# Sheet1.net
KiCad netlist of a schematic drawn in Altium Designer
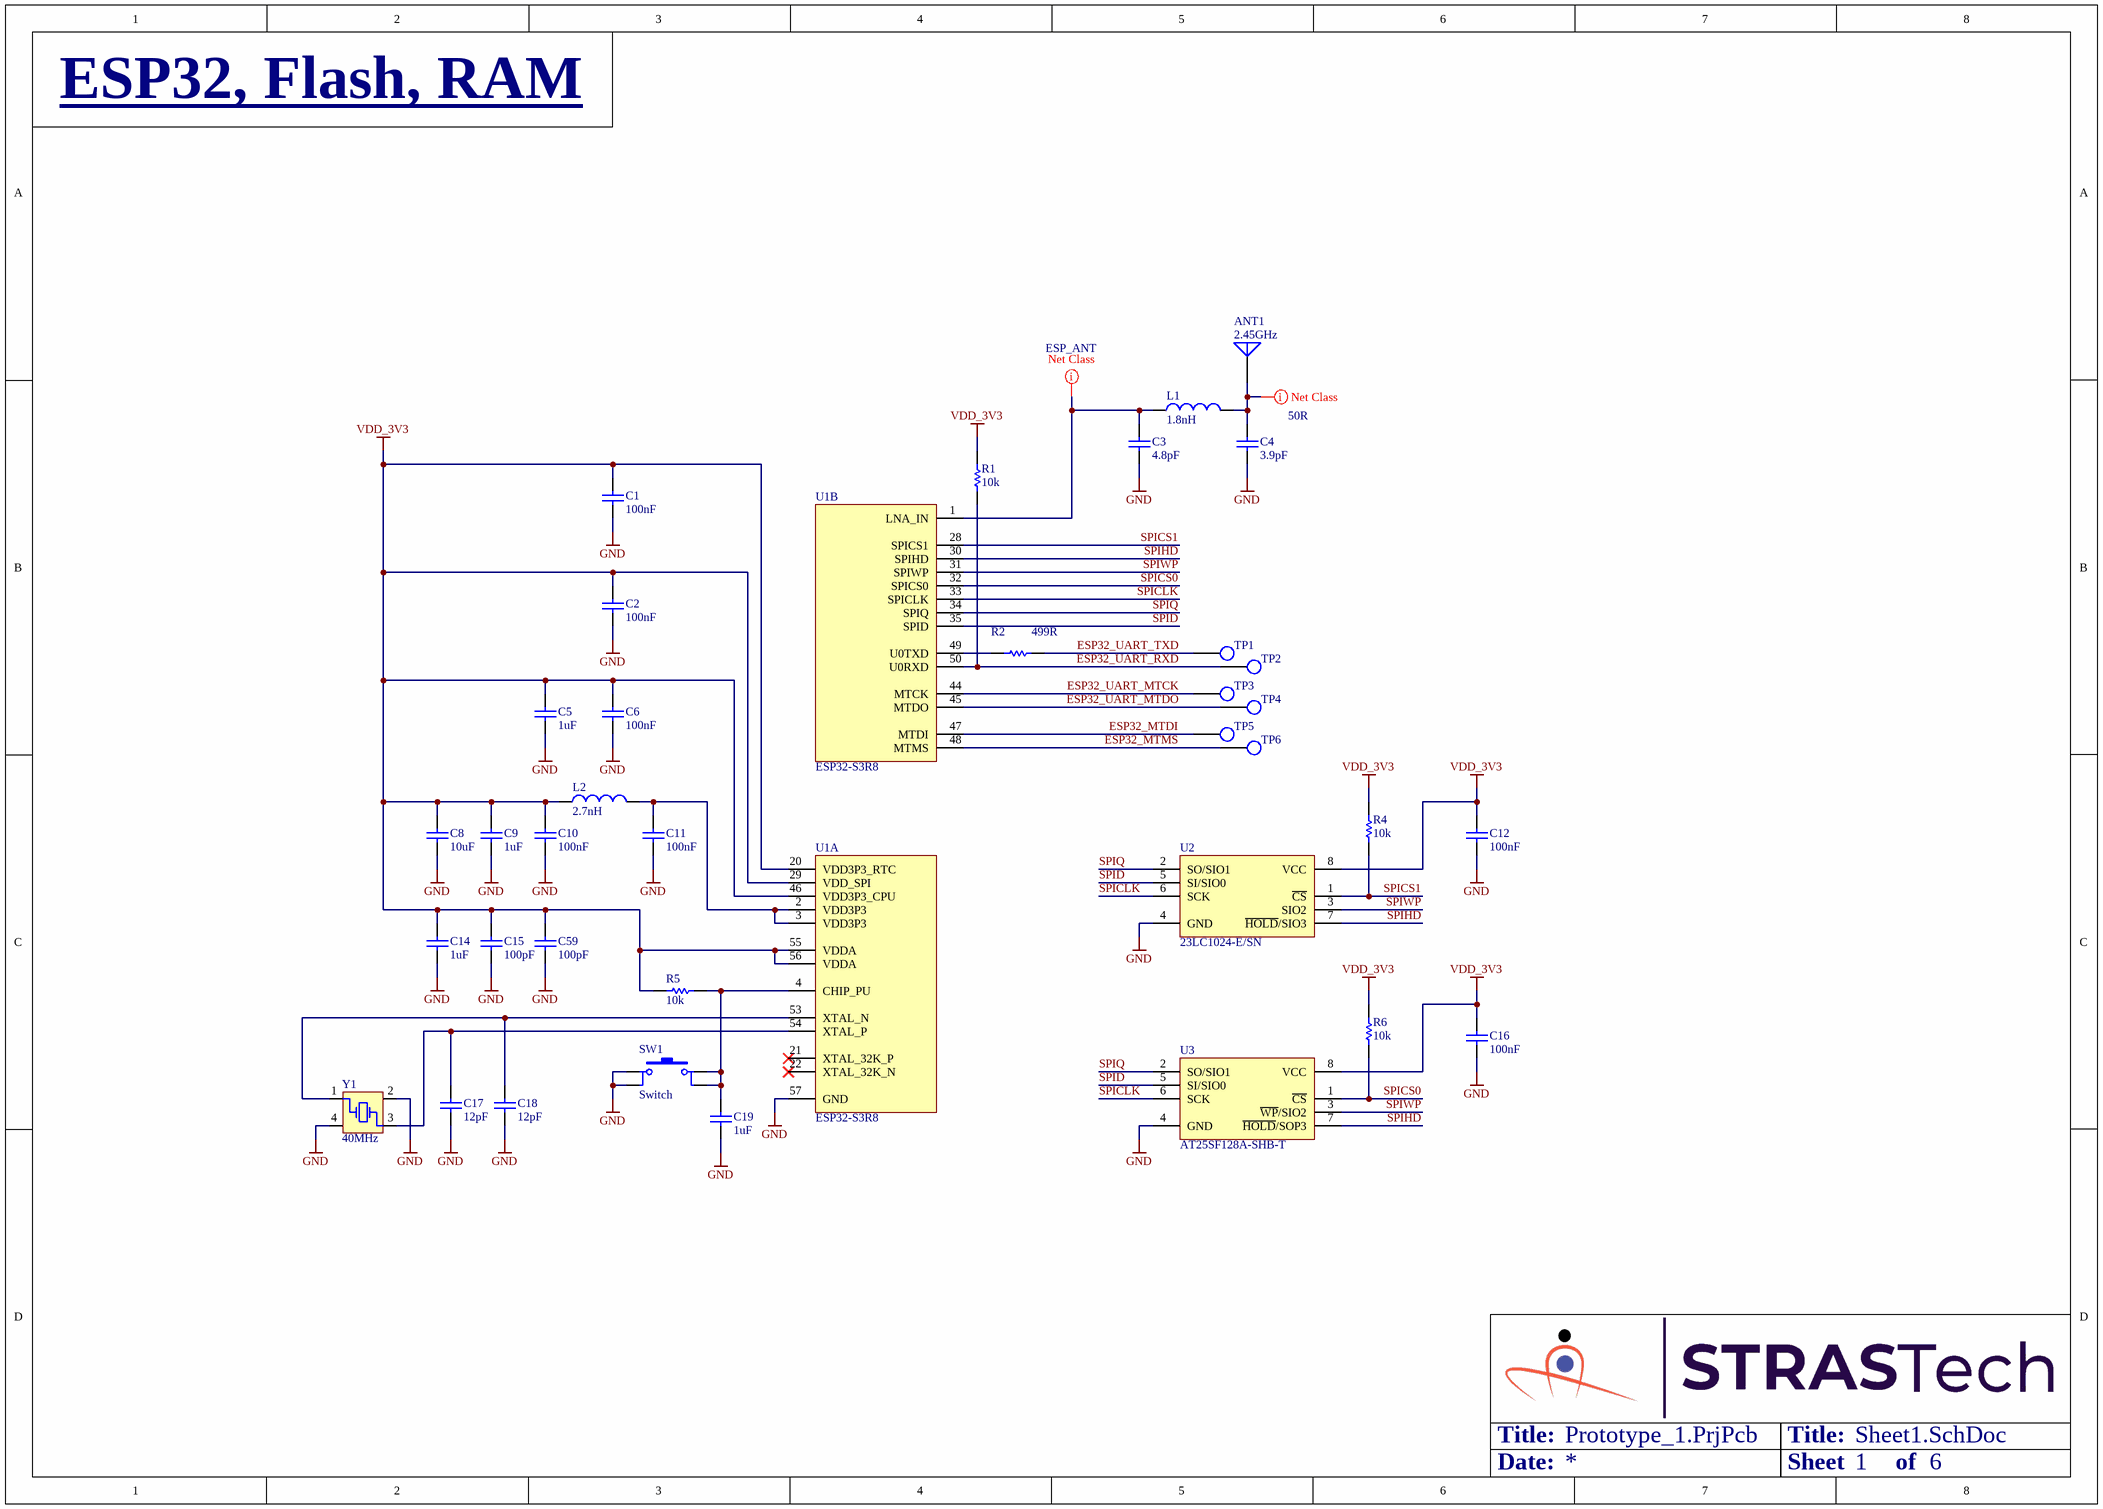
[diagram p0: Sheet1.SchDoc]

(export (version "E")
  (design (tool "Eeschema 10.0.6"))
  (components
    (comp (ref "ANT1")
      (value "2.45GHz")
      (footprint "ANT,PCB,IFA,2.45GHZ")
      (description "2.4-GHz Inverted F Antenna")
      (fields (field (name "CREATEDBY") "Judd Foster"))
      (libsource (lib "symbols") (part "ANT,2.45GHz,IFA,PCB"))
    )
    (comp (ref "C1")
      (value "100nF")
      (footprint "Cap,SMD,0402")
      (description "0.1µF ±10% 25V Ceramic Capacitor X7R 0402 (1005 Metric)")
      (fields
        (field (name "VENDOR PART NUMBER") "490-14603-1-ND")
        (field (name "MANUFACTURER") "Murata Electronics")
        (field (name "CREATEDBY") "Judd Foster")
      )
      (libsource (lib "symbols") (part "CAP,Cer,100nF,25VDC,X7R,0402"))
    )
    (comp (ref "C2")
      (value "100nF")
      (footprint "Cap,SMD,0402")
      (description "0.1µF ±10% 25V Ceramic Capacitor X7R 0402 (1005 Metric)")
      (fields
        (field (name "VENDOR PART NUMBER") "490-14603-1-ND")
        (field (name "MANUFACTURER") "Murata Electronics")
        (field (name "CREATEDBY") "Judd Foster")
      )
      (libsource (lib "symbols") (part "CAP,Cer,100nF,25VDC,X7R,0402"))
    )
    (comp (ref "C3")
      (value "4.8pF")
      (footprint "Cap,SMD,0402")
      (description "4.8 pF ±0.25pF 50V Ceramic Capacitor C0G, NP0 0402 (1005 Metric)")
      (fields
        (field (name "VENDOR PART NUMBER") "490-17481-1-ND")
        (field (name "MANUFACTURER") "Murata Electronics")
        (field (name "CREATEDBY") "Judd Foster")
      )
      (libsource (lib "symbols") (part "CAP,Cer,4.8pF,50VDC,C0G/NP0,0402"))
    )
    (comp (ref "C4")
      (value "3.9pF")
      (footprint "Cap,SMD,0402")
      (description "3.9 pF ±0.1pF 50V Ceramic Capacitor C0G, NP0 0402 (1005 Metric)")
      (fields
        (field (name "VENDOR PART NUMBER") "399-CBR04C399B5GACCT-ND")
        (field (name "MANUFACTURER") "KEMET")
        (field (name "CREATEDBY") "Judd Foster")
      )
      (libsource (lib "symbols") (part "CAP,Cer,3.9pF,50VDC,C0G/NP0,0402"))
    )
    (comp (ref "C5")
      (value "1uF")
      (footprint "Cap,SMD,0402")
      (description "1 µF ±10% 35V Ceramic Capacitor X5R 0402 (1005 Metric)")
      (fields
        (field (name "VENDOR PART NUMBER") "445-9073-1-ND")
        (field (name "MANUFACTURER") "TDK Corporation")
        (field (name "CREATEDBY") "Judd Foster")
      )
      (libsource (lib "symbols") (part "CAP,Cer,1uF,35VDC,X5R,0402"))
    )
    (comp (ref "C6")
      (value "100nF")
      (footprint "Cap,SMD,0402")
      (description "0.1µF ±10% 25V Ceramic Capacitor X7R 0402 (1005 Metric)")
      (fields
        (field (name "VENDOR PART NUMBER") "490-14603-1-ND")
        (field (name "MANUFACTURER") "Murata Electronics")
        (field (name "CREATEDBY") "Judd Foster")
      )
      (libsource (lib "symbols") (part "CAP,Cer,100nF,25VDC,X7R,0402"))
    )
    (comp (ref "C8")
      (value "10uF")
      (footprint "Cap,SMD,0402")
      (description "10 µF ±20% 10V Ceramic Capacitor X5R 0402 (1005 Metric)")
      (fields
        (field (name "VENDOR PART NUMBER") "1276-1450-1-ND")
        (field (name "MANUFACTURER") "Samsung Electro-Mechanics")
        (field (name "CREATEDBY") "Judd Foster")
      )
      (libsource (lib "symbols") (part "CAP,Cer,10uF,10VDC,X5R,0402"))
    )
    (comp (ref "C9")
      (value "1uF")
      (footprint "Cap,SMD,0402")
      (description "1 µF ±10% 35V Ceramic Capacitor X5R 0402 (1005 Metric)")
      (fields
        (field (name "VENDOR PART NUMBER") "445-9073-1-ND")
        (field (name "MANUFACTURER") "TDK Corporation")
        (field (name "CREATEDBY") "Judd Foster")
      )
      (libsource (lib "symbols") (part "CAP,Cer,1uF,35VDC,X5R,0402"))
    )
    (comp (ref "C10")
      (value "100nF")
      (footprint "Cap,SMD,0402")
      (description "0.1µF ±10% 25V Ceramic Capacitor X7R 0402 (1005 Metric)")
      (fields
        (field (name "VENDOR PART NUMBER") "490-14603-1-ND")
        (field (name "MANUFACTURER") "Murata Electronics")
        (field (name "CREATEDBY") "Judd Foster")
      )
      (libsource (lib "symbols") (part "CAP,Cer,100nF,25VDC,X7R,0402"))
    )
    (comp (ref "C11")
      (value "100nF")
      (footprint "Cap,SMD,0402")
      (description "0.1µF ±10% 25V Ceramic Capacitor X7R 0402 (1005 Metric)")
      (fields
        (field (name "VENDOR PART NUMBER") "490-14603-1-ND")
        (field (name "MANUFACTURER") "Murata Electronics")
        (field (name "CREATEDBY") "Judd Foster")
      )
      (libsource (lib "symbols") (part "CAP,Cer,100nF,25VDC,X7R,0402"))
    )
    (comp (ref "C12")
      (value "100nF")
      (footprint "Cap,SMD,0402")
      (description "0.1µF ±10% 25V Ceramic Capacitor X7R 0402 (1005 Metric)")
      (fields
        (field (name "VENDOR PART NUMBER") "490-14603-1-ND")
        (field (name "MANUFACTURER") "Murata Electronics")
        (field (name "CREATEDBY") "Judd Foster")
      )
      (libsource (lib "symbols") (part "CAP,Cer,100nF,25VDC,X7R,0402"))
    )
    (comp (ref "C14")
      (value "1uF")
      (footprint "Cap,SMD,0402")
      (description "1 µF ±10% 35V Ceramic Capacitor X5R 0402 (1005 Metric)")
      (fields
        (field (name "VENDOR PART NUMBER") "445-9073-1-ND")
        (field (name "MANUFACTURER") "TDK Corporation")
        (field (name "CREATEDBY") "Judd Foster")
      )
      (libsource (lib "symbols") (part "CAP,Cer,1uF,35VDC,X5R,0402"))
    )
    (comp (ref "C15")
      (value "100pF")
      (footprint "Cap,SMD,0402")
      (description "100pF ±5% 50V Ceramic Capacitor C0G, NP0 0402 (1005 Metric)")
      (fields
        (field (name "VENDOR PART NUMBER") "490-10669-1-ND")
        (field (name "MANUFACTURER") "Murata Electronics")
        (field (name "CREATEDBY") "Judd Foster")
      )
      (libsource (lib "symbols") (part "CAP,Cer,100pF,50VDC,C0G/NP0,0402"))
    )
    (comp (ref "C16")
      (value "100nF")
      (footprint "Cap,SMD,0402")
      (description "0.1µF ±10% 25V Ceramic Capacitor X7R 0402 (1005 Metric)")
      (fields
        (field (name "VENDOR PART NUMBER") "490-14603-1-ND")
        (field (name "MANUFACTURER") "Murata Electronics")
        (field (name "CREATEDBY") "Judd Foster")
      )
      (libsource (lib "symbols") (part "CAP,Cer,100nF,25VDC,X7R,0402"))
    )
    (comp (ref "C17")
      (value "12pF")
      (footprint "Cap,SMD,0402")
      (description "12pF ±5% 50V Ceramic Capacitor C0G, NP0 0402 (1005 Metric)")
      (fields
        (field (name "VENDOR PART NUMBER") "311-1016-1-ND")
        (field (name "MANUFACTURER") "Yageo")
        (field (name "CREATEDBY") "Judd Foster")
      )
      (libsource (lib "symbols") (part "CAP,Cer,12pF,50VDC,C0G/NP0,0402"))
    )
    (comp (ref "C18")
      (value "12pF")
      (footprint "Cap,SMD,0402")
      (description "12pF ±5% 50V Ceramic Capacitor C0G, NP0 0402 (1005 Metric)")
      (fields
        (field (name "VENDOR PART NUMBER") "311-1016-1-ND")
        (field (name "MANUFACTURER") "Yageo")
        (field (name "CREATEDBY") "Judd Foster")
      )
      (libsource (lib "symbols") (part "CAP,Cer,12pF,50VDC,C0G/NP0,0402"))
    )
    (comp (ref "C19")
      (value "1uF")
      (footprint "Cap,SMD,0402")
      (description "1µF ±20% 6.3V Ceramic Capacitor X5R 0402 (1005 Metric)")
      (fields
        (field (name "VENDOR PART NUMBER") "1276-1235-1-ND")
        (field (name "MANUFACTURER") "Samsung Electro-Mechanics")
        (field (name "CREATEDBY") "Judd Foster")
      )
      (libsource (lib "symbols") (part "CAP,Cer,1uF,6.3VDC,X5R,0402"))
    )
    (comp (ref "C59")
      (value "100pF")
      (footprint "Cap,SMD,0402")
      (description "100pF ±5% 50V Ceramic Capacitor C0G, NP0 0402 (1005 Metric)")
      (fields
        (field (name "VENDOR PART NUMBER") "490-10669-1-ND")
        (field (name "MANUFACTURER") "Murata Electronics")
        (field (name "CREATEDBY") "Judd Foster")
      )
      (libsource (lib "symbols") (part "CAP,Cer,100pF,50VDC,C0G/NP0,0402"))
    )
    (comp (ref "L1")
      (value "1.8nH")
      (footprint "ind,0402")
      (description "1.8 nH Unshielded Multilayer Inductor 900 mA 100mOhm Max 0402 (1005 Metric)")
      (fields
        (field (name "VENDOR PART NUMBER") "490-1076-1-ND")
        (field (name "MANUFACTURER") "Murata Electronics")
        (field (name "CREATEDBY") "Judd Foster")
      )
      (libsource (lib "symbols") (part "IND,1.8nH,900mA,Multilayer,0402"))
    )
    (comp (ref "L2")
      (value "2.7nH")
      (footprint "ind,0402")
      (description "2.7nH Unshielded Multilayer Inductor 800mA 150mOhm Max 0402 (1005 Metric)")
      (fields
        (field (name "VENDOR PART NUMBER") "490-2615-1-ND")
        (field (name "MANUFACTURER") "Murata Electronics")
        (field (name "CREATEDBY") "Judd Foster")
      )
      (libsource (lib "symbols") (part "IND,2.7nH,800mA,Multilayer,0402"))
    )
    (comp (ref "R1")
      (value "10k")
      (footprint "RES,0402")
      (description "10 kOhms ±5% 0.063W, 1/16W Chip Resistor 0402 (1005 Metric) Automotive AEC-Q200 Thick Film")
      (fields
        (field (name "VENDOR PART NUMBER") "RMCF0402JT10K0CT-ND")
        (field (name "MANUFACTURER") "Stackpole Electronics Inc")
        (field (name "CREATEDBY") "Judd Foster")
      )
      (libsource (lib "symbols") (part "RES,10k,5%,0.063W,0402"))
    )
    (comp (ref "R2")
      (value "499R")
      (footprint "RES,0402")
      (description "499 Ohms ±1% 0.063W, 1/16W Chip Resistor 0402 (1005 Metric) Automotive AEC-Q200 Thick Film")
      (fields
        (field (name "MANUFACTURER") "Stackpole Electronics Inc")
        (field (name "MANUFACTURER PART NUMBER") "RMCF0402FT499R")
        (field (name "CREATEDBY") "Judd Foster")
      )
      (libsource (lib "symbols") (part "RES,499R,1%,0.063W,0402"))
    )
    (comp (ref "R4")
      (value "10k")
      (footprint "RES,0402")
      (description "10 kOhms ±5% 0.063W, 1/16W Chip Resistor 0402 (1005 Metric) Automotive AEC-Q200 Thick Film")
      (fields
        (field (name "VENDOR PART NUMBER") "RMCF0402JT10K0CT-ND")
        (field (name "MANUFACTURER") "Stackpole Electronics Inc")
        (field (name "CREATEDBY") "Judd Foster")
      )
      (libsource (lib "symbols") (part "RES,10k,5%,0.063W,0402"))
    )
    (comp (ref "R5")
      (value "10k")
      (footprint "RES,0402")
      (description "10 kOhms ±5% 0.063W, 1/16W Chip Resistor 0402 (1005 Metric) Automotive AEC-Q200 Thick Film")
      (fields
        (field (name "VENDOR PART NUMBER") "RMCF0402JT10K0CT-ND")
        (field (name "MANUFACTURER") "Stackpole Electronics Inc")
        (field (name "CREATEDBY") "Judd Foster")
      )
      (libsource (lib "symbols") (part "RES,10k,5%,0.063W,0402"))
    )
    (comp (ref "R6")
      (value "10k")
      (footprint "RES,0402")
      (description "10 kOhms ±5% 0.063W, 1/16W Chip Resistor 0402 (1005 Metric) Automotive AEC-Q200 Thick Film")
      (fields
        (field (name "VENDOR PART NUMBER") "RMCF0402JT10K0CT-ND")
        (field (name "MANUFACTURER") "Stackpole Electronics Inc")
        (field (name "CREATEDBY") "Judd Foster")
      )
      (libsource (lib "symbols") (part "RES,10k,5%,0.063W,0402"))
    )
    (comp (ref "SW1")
      (value "Switch")
      (footprint "Switch,Tactile,Micro,SPST-NO,SMD")
      (description "Tactile Switch SPST-NO Top Actuated Surface Mount")
      (fields
        (field (name "MANUFACTURER") "C&K")
        (field (name "MANUFACTURER PART NUMBER") "PTS525SM15SMTR2 LFS")
        (field (name "CREATEDBY") "Judd Foster")
      )
      (libsource (lib "symbols") (part "Switch,Tactile,SPST-NO,SMD,H1.5"))
    )
    (comp (ref "TP1")
      (value "TESTPOINT")
      (footprint "testpoint,smd,round,1mm")
      (description "PCB Testpoint")
      (fields (field (name "CREATEDBY") "Judd Foster"))
      (libsource (lib "symbols") (part "TESTPOINT"))
    )
    (comp (ref "TP2")
      (value "TESTPOINT")
      (footprint "testpoint,smd,round,1mm")
      (description "PCB Testpoint")
      (fields (field (name "CREATEDBY") "Judd Foster"))
      (libsource (lib "symbols") (part "TESTPOINT"))
    )
    (comp (ref "TP3")
      (value "TESTPOINT")
      (footprint "testpoint,smd,round,1mm")
      (description "PCB Testpoint")
      (fields (field (name "CREATEDBY") "Judd Foster"))
      (libsource (lib "symbols") (part "TESTPOINT"))
    )
    (comp (ref "TP4")
      (value "TESTPOINT")
      (footprint "testpoint,smd,round,1mm")
      (description "PCB Testpoint")
      (fields (field (name "CREATEDBY") "Judd Foster"))
      (libsource (lib "symbols") (part "TESTPOINT"))
    )
    (comp (ref "TP5")
      (value "TESTPOINT")
      (footprint "testpoint,smd,round,1mm")
      (description "PCB Testpoint")
      (fields (field (name "CREATEDBY") "Judd Foster"))
      (libsource (lib "symbols") (part "TESTPOINT"))
    )
    (comp (ref "TP6")
      (value "TESTPOINT")
      (footprint "testpoint,smd,round,1mm")
      (description "PCB Testpoint")
      (fields (field (name "CREATEDBY") "Judd Foster"))
      (libsource (lib "symbols") (part "TESTPOINT"))
    )
    (comp (ref "U1")
      (value "ESP32-S3R8")
      (footprint "IC,QFN-56,7X7,P0.4MM")
      (fields
        (field (name "MANUFACTURER") "Espressif Systems")
        (field (name "VENDOR PART NUMBER") "1904-ESP32-S3R8-ND")
        (field (name "CREATEDBY") "Judd Foster")
      )
      (libsource (lib "") (part "ESP32-S3R8_1"))
    )
    (comp (ref "U2")
      (value "23LC1024-E/SN")
      (footprint "IC,SOIC-8,1.27mm,W3.9")
      (description "SRAM Memory IC 1Mb (128K x 8) SPI - Quad I/O 16 MHz 8-SOIC")
      (fields
        (field (name "MANUFACTURER") "Microchip Technology")
        (field (name "VENDOR PART NUMBER") "23LC1024-E/SN-ND")
        (field (name "CREATEDBY") "Judd Foster")
      )
      (libsource (lib "symbols") (part "23LC1024-E/SN"))
    )
    (comp (ref "U3")
      (value "AT25SF128A-SHB-T")
      (footprint "IC,SOIC-8,1.27mm,W3.9")
      (description "FLASH - NOR Memory IC 128Mb (16M x 8) SPI - Quad I/O 133 MHz 8-SOIC")
      (fields
        (field (name "MANUFACTURER") "Adesto Technologies")
        (field (name "VENDOR PART NUMBER") "1265-1348-1-ND")
        (field (name "CREATEDBY") "Judd Foster")
      )
      (libsource (lib "symbols") (part "AT25SF128A-SHB-T"))
    )
    (comp (ref "Y1")
      (value "40MHz")
      (footprint "XTAL,SMD,4 Pin,2x2.5mm")
      (description "40 MHz ±7ppm Crystal 12pF 25 Ohms 4-SMD, No Lead")
      (fields
        (field (name "MANUFACTURER") "Hosonic Electronic Co., Ltd")
        (field (name "MANUFACTURER PART NUMBER") "E2SB40E000104E")
        (field (name "CREATEDBY") "Judd Foster")
      )
      (libsource (lib "symbols") (part "XTAL,40MHz,12pF,SMD"))
    )
  )
  (nets
    (net (code "1") (name "/ESP32_MTDI") (class "Default")
      (node (ref "TP5") (pin "1") (pinfunction "TP_1") (pintype "passive"))
      (node (ref "U1") (pin "47") (pinfunction "MTDI_47") (pintype "passive"))
    )
    (net (code "2") (name "/ESP32_MTMS") (class "Default")
      (node (ref "TP6") (pin "1") (pinfunction "TP_1") (pintype "passive"))
      (node (ref "U1") (pin "48") (pinfunction "MTMS_48") (pintype "passive"))
    )
    (net (code "3") (name "/ESP32_UART_MTCK") (class "Default")
      (node (ref "TP3") (pin "1") (pinfunction "TP_1") (pintype "passive"))
      (node (ref "U1") (pin "44") (pinfunction "MTCK_44") (pintype "passive"))
    )
    (net (code "4") (name "/ESP32_UART_MTDO") (class "Default")
      (node (ref "TP4") (pin "1") (pinfunction "TP_1") (pintype "passive"))
      (node (ref "U1") (pin "45") (pinfunction "MTDO_45") (pintype "passive"))
    )
    (net (code "5") (name "/ESP32_UART_RXD") (class "Default")
      (node (ref "R1") (pin "1") (pinfunction "1_1") (pintype "passive"))
      (node (ref "TP2") (pin "1") (pinfunction "TP_1") (pintype "passive"))
      (node (ref "U1") (pin "50") (pinfunction "U0RXD_50") (pintype "passive"))
    )
    (net (code "6") (name "/ESP32_UART_TXD") (class "Default")
      (node (ref "R2") (pin "2") (pinfunction "2_2") (pintype "passive"))
      (node (ref "TP1") (pin "1") (pinfunction "TP_1") (pintype "passive"))
    )
    (net (code "7") (name "/SPICLK") (class "Default")
      (node (ref "U1") (pin "33") (pinfunction "SPICLK_33") (pintype "passive"))
      (node (ref "U2") (pin "6") (pinfunction "SCK_6") (pintype "passive"))
      (node (ref "U3") (pin "6") (pinfunction "SCK_6") (pintype "passive"))
    )
    (net (code "8") (name "/SPICS0") (class "Default")
      (node (ref "R6") (pin "1") (pinfunction "1_1") (pintype "passive"))
      (node (ref "U1") (pin "32") (pinfunction "SPICS0_32") (pintype "passive"))
      (node (ref "U3") (pin "1") (pinfunction "~{CS}_1") (pintype "passive"))
    )
    (net (code "9") (name "/SPICS1") (class "Default")
      (node (ref "R4") (pin "1") (pinfunction "1_1") (pintype "passive"))
      (node (ref "U1") (pin "28") (pinfunction "SPICS1_28") (pintype "passive"))
      (node (ref "U2") (pin "1") (pinfunction "~{CS}_1") (pintype "passive"))
    )
    (net (code "10") (name "/SPID") (class "Default")
      (node (ref "U1") (pin "35") (pinfunction "SPID_35") (pintype "passive"))
      (node (ref "U2") (pin "5") (pinfunction "SI/SIO0_5") (pintype "passive"))
      (node (ref "U3") (pin "5") (pinfunction "SI/SIO0_5") (pintype "passive"))
    )
    (net (code "11") (name "/SPIHD") (class "Default")
      (node (ref "U1") (pin "30") (pinfunction "SPIHD_30") (pintype "passive"))
      (node (ref "U2") (pin "7") (pinfunction "~{HOLD}/SIO3_7") (pintype "passive"))
      (node (ref "U3") (pin "7") (pinfunction "~{HOLD}/SOP3_7") (pintype "passive"))
    )
    (net (code "12") (name "/SPIQ") (class "Default")
      (node (ref "U1") (pin "34") (pinfunction "SPIQ_34") (pintype "passive"))
      (node (ref "U2") (pin "2") (pinfunction "SO/SIO1_2") (pintype "passive"))
      (node (ref "U3") (pin "2") (pinfunction "SO/SIO1_2") (pintype "passive"))
    )
    (net (code "13") (name "/SPIWP") (class "Default")
      (node (ref "U1") (pin "31") (pinfunction "SPIWP_31") (pintype "passive"))
      (node (ref "U2") (pin "3") (pinfunction "SIO2_3") (pintype "passive"))
      (node (ref "U3") (pin "3") (pinfunction "~{WP}/SIO2_3") (pintype "passive"))
    )
    (net (code "14") (name "GND") (class "Default")
      (node (ref "C1") (pin "1") (pinfunction "1_1") (pintype "passive"))
      (node (ref "C10") (pin "1") (pinfunction "1_1") (pintype "passive"))
      (node (ref "C11") (pin "1") (pinfunction "1_1") (pintype "passive"))
      (node (ref "C12") (pin "1") (pinfunction "1_1") (pintype "passive"))
      (node (ref "C14") (pin "1") (pinfunction "1_1") (pintype "passive"))
      (node (ref "C15") (pin "1") (pinfunction "1_1") (pintype "passive"))
      (node (ref "C16") (pin "1") (pinfunction "1_1") (pintype "passive"))
      (node (ref "C17") (pin "2") (pinfunction "2_2") (pintype "passive"))
      (node (ref "C18") (pin "2") (pinfunction "2_2") (pintype "passive"))
      (node (ref "C19") (pin "1") (pinfunction "1_1") (pintype "passive"))
      (node (ref "C2") (pin "1") (pinfunction "1_1") (pintype "passive"))
      (node (ref "C3") (pin "1") (pinfunction "1_1") (pintype "passive"))
      (node (ref "C4") (pin "1") (pinfunction "1_1") (pintype "passive"))
      (node (ref "C5") (pin "1") (pinfunction "1_1") (pintype "passive"))
      (node (ref "C59") (pin "1") (pinfunction "1_1") (pintype "passive"))
      (node (ref "C6") (pin "1") (pinfunction "1_1") (pintype "passive"))
      (node (ref "C8") (pin "1") (pinfunction "1_1") (pintype "passive"))
      (node (ref "C9") (pin "1") (pinfunction "1_1") (pintype "passive"))
      (node (ref "SW1") (pin "1") (pinfunction "1_1") (pintype "passive"))
      (node (ref "SW1") (pin "2") (pinfunction "2_2") (pintype "passive"))
      (node (ref "U1") (pin "57") (pinfunction "GND_57") (pintype "passive"))
      (node (ref "U2") (pin "4") (pinfunction "GND_4") (pintype "passive"))
      (node (ref "U3") (pin "4") (pinfunction "GND_4") (pintype "passive"))
      (node (ref "Y1") (pin "2") (pinfunction "GND_2") (pintype "passive"))
      (node (ref "Y1") (pin "4") (pinfunction "GND_4") (pintype "passive"))
    )
    (net (code "15") (name "Net-(ANT1-Pad1)") (class "Default")
      (node (ref "ANT1") (pin "1") (pinfunction "1_1") (pintype "passive"))
      (node (ref "C4") (pin "2") (pinfunction "2_2") (pintype "passive"))
      (node (ref "L1") (pin "2") (pinfunction "2_2") (pintype "passive"))
    )
    (net (code "16") (name "Net-(C11-Pad2)") (class "Default")
      (node (ref "C11") (pin "2") (pinfunction "2_2") (pintype "passive"))
      (node (ref "L2") (pin "2") (pinfunction "2_2") (pintype "passive"))
      (node (ref "U1") (pin "2") (pinfunction "VDD3P3_2") (pintype "passive"))
      (node (ref "U1") (pin "3") (pinfunction "VDD3P3_3") (pintype "passive"))
    )
    (net (code "17") (name "Net-(U1A-CHIP_PU)") (class "Default")
      (node (ref "C19") (pin "2") (pinfunction "2_2") (pintype "passive"))
      (node (ref "R5") (pin "1") (pinfunction "1_1") (pintype "passive"))
      (node (ref "SW1") (pin "3") (pinfunction "3_3") (pintype "passive"))
      (node (ref "SW1") (pin "4") (pinfunction "4_4") (pintype "passive"))
      (node (ref "U1") (pin "4") (pinfunction "CHIP_PU_4") (pintype "passive"))
    )
    (net (code "18") (name "Net-(U1A-XTAL_N)") (class "Default")
      (node (ref "C18") (pin "1") (pinfunction "1_1") (pintype "passive"))
      (node (ref "U1") (pin "53") (pinfunction "XTAL_N_53") (pintype "passive"))
      (node (ref "Y1") (pin "1") (pinfunction "OSC1_1") (pintype "passive"))
    )
    (net (code "19") (name "Net-(U1A-XTAL_P)") (class "Default")
      (node (ref "C17") (pin "1") (pinfunction "1_1") (pintype "passive"))
      (node (ref "U1") (pin "54") (pinfunction "XTAL_P_54") (pintype "passive"))
      (node (ref "Y1") (pin "3") (pinfunction "OSC2_3") (pintype "passive"))
    )
    (net (code "20") (name "Net-(U1B-LNA_IN)") (class "Default")
      (node (ref "C3") (pin "2") (pinfunction "2_2") (pintype "passive"))
      (node (ref "L1") (pin "1") (pinfunction "1_1") (pintype "passive"))
      (node (ref "U1") (pin "1") (pinfunction "LNA_IN_1") (pintype "passive"))
    )
    (net (code "21") (name "Net-(U1B-U0TXD)") (class "Default")
      (node (ref "R2") (pin "1") (pinfunction "1_1") (pintype "passive"))
      (node (ref "U1") (pin "49") (pinfunction "U0TXD_49") (pintype "passive"))
    )
    (net (code "22") (name "VDD_3V3") (class "Default")
      (node (ref "C1") (pin "2") (pinfunction "2_2") (pintype "passive"))
      (node (ref "C10") (pin "2") (pinfunction "2_2") (pintype "passive"))
      (node (ref "C12") (pin "2") (pinfunction "2_2") (pintype "passive"))
      (node (ref "C14") (pin "2") (pinfunction "2_2") (pintype "passive"))
      (node (ref "C15") (pin "2") (pinfunction "2_2") (pintype "passive"))
      (node (ref "C16") (pin "2") (pinfunction "2_2") (pintype "passive"))
      (node (ref "C2") (pin "2") (pinfunction "2_2") (pintype "passive"))
      (node (ref "C5") (pin "2") (pinfunction "2_2") (pintype "passive"))
      (node (ref "C59") (pin "2") (pinfunction "2_2") (pintype "passive"))
      (node (ref "C6") (pin "2") (pinfunction "2_2") (pintype "passive"))
      (node (ref "C8") (pin "2") (pinfunction "2_2") (pintype "passive"))
      (node (ref "C9") (pin "2") (pinfunction "2_2") (pintype "passive"))
      (node (ref "L2") (pin "1") (pinfunction "1_1") (pintype "passive"))
      (node (ref "R1") (pin "2") (pinfunction "2_2") (pintype "passive"))
      (node (ref "R4") (pin "2") (pinfunction "2_2") (pintype "passive"))
      (node (ref "R5") (pin "2") (pinfunction "2_2") (pintype "passive"))
      (node (ref "R6") (pin "2") (pinfunction "2_2") (pintype "passive"))
      (node (ref "U1") (pin "20") (pinfunction "VDD3P3_RTC_20") (pintype "passive"))
      (node (ref "U1") (pin "29") (pinfunction "VDD_SPI_29") (pintype "passive"))
      (node (ref "U1") (pin "46") (pinfunction "VDD3P3_CPU_46") (pintype "passive"))
      (node (ref "U1") (pin "55") (pinfunction "VDDA_55") (pintype "passive"))
      (node (ref "U1") (pin "56") (pinfunction "VDDA_56") (pintype "passive"))
      (node (ref "U2") (pin "8") (pinfunction "VCC_8") (pintype "passive"))
      (node (ref "U3") (pin "8") (pinfunction "VCC_8") (pintype "passive"))
    )
    (net (code "23") (name "unconnected-(U1A-XTAL_32K_N-Pad22)") (class "Default")
      (node (ref "U1") (pin "22") (pinfunction "XTAL_32K_N_22") (pintype "passive+no_connect"))
    )
    (net (code "24") (name "unconnected-(U1A-XTAL_32K_P-Pad21)") (class "Default")
      (node (ref "U1") (pin "21") (pinfunction "XTAL_32K_P_21") (pintype "passive+no_connect"))
    )
  )
)
